# 780-00031_rev1_BlackFin_Shorting_Block.net
KiCad netlist of a schematic drawn in Altium Designer
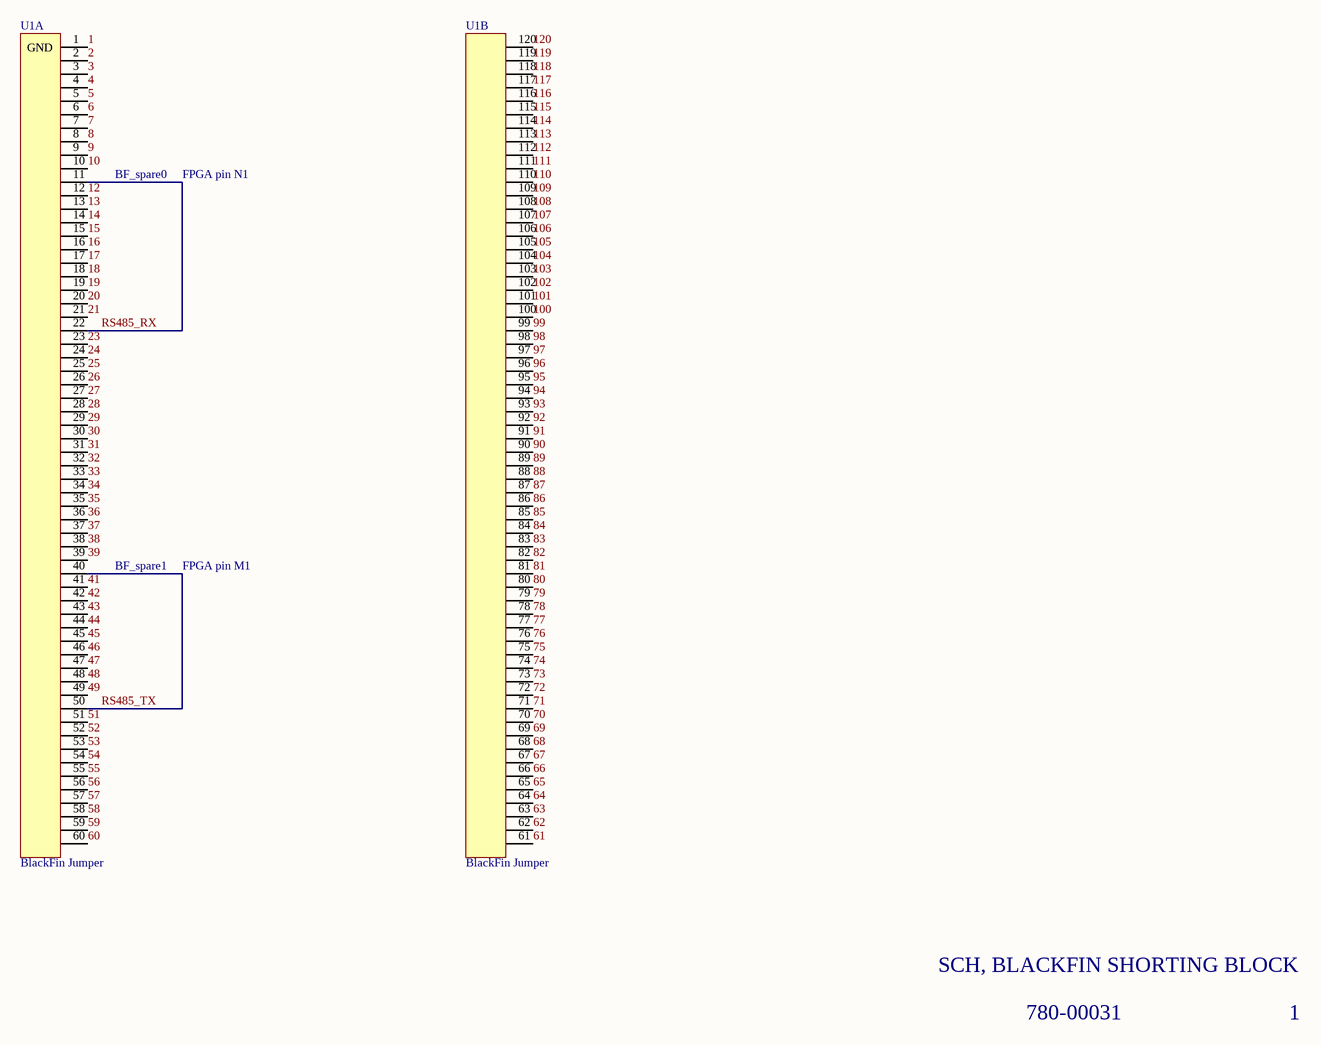
[diagram p0: 780-00031, rev1, BlackFin Shorting Block.SchDoc]

(export (version "E")
  (design (tool "Eeschema 10.0.6"))
  (components
    (comp (ref "U1")
      (value "BlackFin Jumper")
      (footprint "CM-BF5xx - Shorting Block")
      (description "Jumper to replace BF with shorting block")
      (libsource (lib "") (part "BlackFin Jumper_1"))
    )
  )
  (nets
    (net (code "1") (name "/1") (class "Default")
      (node (ref "U1") (pin "1") (pinfunction "GND_1") (pintype "passive"))
    )
    (net (code "2") (name "/2") (class "Default") (node (ref "U1") (pin "2") (pintype "passive")))
    (net (code "3") (name "/3") (class "Default") (node (ref "U1") (pin "3") (pintype "passive")))
    (net (code "4") (name "/4") (class "Default") (node (ref "U1") (pin "4") (pintype "passive")))
    (net (code "5") (name "/5") (class "Default") (node (ref "U1") (pin "5") (pintype "passive")))
    (net (code "6") (name "/6") (class "Default") (node (ref "U1") (pin "6") (pintype "passive")))
    (net (code "7") (name "/7") (class "Default") (node (ref "U1") (pin "7") (pintype "passive")))
    (net (code "8") (name "/8") (class "Default") (node (ref "U1") (pin "8") (pintype "passive")))
    (net (code "9") (name "/9") (class "Default") (node (ref "U1") (pin "9") (pintype "passive")))
    (net (code "10") (name "/10") (class "Default") (node (ref "U1") (pin "10") (pintype "passive")))
    (net (code "11") (name "/12") (class "Default") (node (ref "U1") (pin "12") (pintype "passive")))
    (net (code "12") (name "/13") (class "Default") (node (ref "U1") (pin "13") (pintype "passive")))
    (net (code "13") (name "/14") (class "Default") (node (ref "U1") (pin "14") (pintype "passive")))
    (net (code "14") (name "/15") (class "Default") (node (ref "U1") (pin "15") (pintype "passive")))
    (net (code "15") (name "/16") (class "Default") (node (ref "U1") (pin "16") (pintype "passive")))
    (net (code "16") (name "/17") (class "Default") (node (ref "U1") (pin "17") (pintype "passive")))
    (net (code "17") (name "/18") (class "Default") (node (ref "U1") (pin "18") (pintype "passive")))
    (net (code "18") (name "/19") (class "Default") (node (ref "U1") (pin "19") (pintype "passive")))
    (net (code "19") (name "/20") (class "Default") (node (ref "U1") (pin "20") (pintype "passive")))
    (net (code "20") (name "/21") (class "Default") (node (ref "U1") (pin "21") (pintype "passive")))
    (net (code "21") (name "/23") (class "Default") (node (ref "U1") (pin "23") (pintype "passive")))
    (net (code "22") (name "/24") (class "Default") (node (ref "U1") (pin "24") (pintype "passive")))
    (net (code "23") (name "/25") (class "Default") (node (ref "U1") (pin "25") (pintype "passive")))
    (net (code "24") (name "/26") (class "Default") (node (ref "U1") (pin "26") (pintype "passive")))
    (net (code "25") (name "/27") (class "Default") (node (ref "U1") (pin "27") (pintype "passive")))
    (net (code "26") (name "/28") (class "Default") (node (ref "U1") (pin "28") (pintype "passive")))
    (net (code "27") (name "/29") (class "Default") (node (ref "U1") (pin "29") (pintype "passive")))
    (net (code "28") (name "/30") (class "Default") (node (ref "U1") (pin "30") (pintype "passive")))
    (net (code "29") (name "/31") (class "Default") (node (ref "U1") (pin "31") (pintype "passive")))
    (net (code "30") (name "/32") (class "Default") (node (ref "U1") (pin "32") (pintype "passive")))
    (net (code "31") (name "/33") (class "Default") (node (ref "U1") (pin "33") (pintype "passive")))
    (net (code "32") (name "/34") (class "Default") (node (ref "U1") (pin "34") (pintype "passive")))
    (net (code "33") (name "/35") (class "Default") (node (ref "U1") (pin "35") (pintype "passive")))
    (net (code "34") (name "/36") (class "Default") (node (ref "U1") (pin "36") (pintype "passive")))
    (net (code "35") (name "/37") (class "Default") (node (ref "U1") (pin "37") (pintype "passive")))
    (net (code "36") (name "/38") (class "Default") (node (ref "U1") (pin "38") (pintype "passive")))
    (net (code "37") (name "/39") (class "Default") (node (ref "U1") (pin "39") (pintype "passive")))
    (net (code "38") (name "/41") (class "Default") (node (ref "U1") (pin "41") (pintype "passive")))
    (net (code "39") (name "/42") (class "Default") (node (ref "U1") (pin "42") (pintype "passive")))
    (net (code "40") (name "/43") (class "Default") (node (ref "U1") (pin "43") (pintype "passive")))
    (net (code "41") (name "/44") (class "Default") (node (ref "U1") (pin "44") (pintype "passive")))
    (net (code "42") (name "/45") (class "Default") (node (ref "U1") (pin "45") (pintype "passive")))
    (net (code "43") (name "/46") (class "Default") (node (ref "U1") (pin "46") (pintype "passive")))
    (net (code "44") (name "/47") (class "Default") (node (ref "U1") (pin "47") (pintype "passive")))
    (net (code "45") (name "/48") (class "Default") (node (ref "U1") (pin "48") (pintype "passive")))
    (net (code "46") (name "/49") (class "Default") (node (ref "U1") (pin "49") (pintype "passive")))
    (net (code "47") (name "/51") (class "Default") (node (ref "U1") (pin "51") (pintype "passive")))
    (net (code "48") (name "/52") (class "Default") (node (ref "U1") (pin "52") (pintype "passive")))
    (net (code "49") (name "/53") (class "Default") (node (ref "U1") (pin "53") (pintype "passive")))
    (net (code "50") (name "/54") (class "Default") (node (ref "U1") (pin "54") (pintype "passive")))
    (net (code "51") (name "/55") (class "Default") (node (ref "U1") (pin "55") (pintype "passive")))
    (net (code "52") (name "/56") (class "Default") (node (ref "U1") (pin "56") (pintype "passive")))
    (net (code "53") (name "/57") (class "Default") (node (ref "U1") (pin "57") (pintype "passive")))
    (net (code "54") (name "/58") (class "Default") (node (ref "U1") (pin "58") (pintype "passive")))
    (net (code "55") (name "/59") (class "Default") (node (ref "U1") (pin "59") (pintype "passive")))
    (net (code "56") (name "/60") (class "Default") (node (ref "U1") (pin "60") (pintype "passive")))
    (net (code "57") (name "/61") (class "Default") (node (ref "U1") (pin "61") (pintype "passive")))
    (net (code "58") (name "/62") (class "Default") (node (ref "U1") (pin "62") (pintype "passive")))
    (net (code "59") (name "/63") (class "Default") (node (ref "U1") (pin "63") (pintype "passive")))
    (net (code "60") (name "/64") (class "Default") (node (ref "U1") (pin "64") (pintype "passive")))
    (net (code "61") (name "/65") (class "Default") (node (ref "U1") (pin "65") (pintype "passive")))
    (net (code "62") (name "/66") (class "Default") (node (ref "U1") (pin "66") (pintype "passive")))
    (net (code "63") (name "/67") (class "Default") (node (ref "U1") (pin "67") (pintype "passive")))
    (net (code "64") (name "/68") (class "Default") (node (ref "U1") (pin "68") (pintype "passive")))
    (net (code "65") (name "/69") (class "Default") (node (ref "U1") (pin "69") (pintype "passive")))
    (net (code "66") (name "/70") (class "Default") (node (ref "U1") (pin "70") (pintype "passive")))
    (net (code "67") (name "/71") (class "Default") (node (ref "U1") (pin "71") (pintype "passive")))
    (net (code "68") (name "/72") (class "Default") (node (ref "U1") (pin "72") (pintype "passive")))
    (net (code "69") (name "/73") (class "Default") (node (ref "U1") (pin "73") (pintype "passive")))
    (net (code "70") (name "/74") (class "Default") (node (ref "U1") (pin "74") (pintype "passive")))
    (net (code "71") (name "/75") (class "Default") (node (ref "U1") (pin "75") (pintype "passive")))
    (net (code "72") (name "/76") (class "Default") (node (ref "U1") (pin "76") (pintype "passive")))
    (net (code "73") (name "/77") (class "Default") (node (ref "U1") (pin "77") (pintype "passive")))
    (net (code "74") (name "/78") (class "Default") (node (ref "U1") (pin "78") (pintype "passive")))
    (net (code "75") (name "/79") (class "Default") (node (ref "U1") (pin "79") (pintype "passive")))
    (net (code "76") (name "/80") (class "Default") (node (ref "U1") (pin "80") (pintype "passive")))
    (net (code "77") (name "/81") (class "Default") (node (ref "U1") (pin "81") (pintype "passive")))
    (net (code "78") (name "/82") (class "Default") (node (ref "U1") (pin "82") (pintype "passive")))
    (net (code "79") (name "/83") (class "Default") (node (ref "U1") (pin "83") (pintype "passive")))
    (net (code "80") (name "/84") (class "Default") (node (ref "U1") (pin "84") (pintype "passive")))
    (net (code "81") (name "/85") (class "Default") (node (ref "U1") (pin "85") (pintype "passive")))
    (net (code "82") (name "/86") (class "Default") (node (ref "U1") (pin "86") (pintype "passive")))
    (net (code "83") (name "/87") (class "Default") (node (ref "U1") (pin "87") (pintype "passive")))
    (net (code "84") (name "/88") (class "Default") (node (ref "U1") (pin "88") (pintype "passive")))
    (net (code "85") (name "/89") (class "Default") (node (ref "U1") (pin "89") (pintype "passive")))
    (net (code "86") (name "/90") (class "Default") (node (ref "U1") (pin "90") (pintype "passive")))
    (net (code "87") (name "/91") (class "Default") (node (ref "U1") (pin "91") (pintype "passive")))
    (net (code "88") (name "/92") (class "Default") (node (ref "U1") (pin "92") (pintype "passive")))
    (net (code "89") (name "/93") (class "Default") (node (ref "U1") (pin "93") (pintype "passive")))
    (net (code "90") (name "/94") (class "Default") (node (ref "U1") (pin "94") (pintype "passive")))
    (net (code "91") (name "/95") (class "Default") (node (ref "U1") (pin "95") (pintype "passive")))
    (net (code "92") (name "/96") (class "Default") (node (ref "U1") (pin "96") (pintype "passive")))
    (net (code "93") (name "/97") (class "Default") (node (ref "U1") (pin "97") (pintype "passive")))
    (net (code "94") (name "/98") (class "Default") (node (ref "U1") (pin "98") (pintype "passive")))
    (net (code "95") (name "/99") (class "Default") (node (ref "U1") (pin "99") (pintype "passive")))
    (net (code "96") (name "/100") (class "Default") (node (ref "U1") (pin "100") (pintype "passive")))
    (net (code "97") (name "/101") (class "Default") (node (ref "U1") (pin "101") (pintype "passive")))
    (net (code "98") (name "/102") (class "Default") (node (ref "U1") (pin "102") (pintype "passive")))
    (net (code "99") (name "/103") (class "Default") (node (ref "U1") (pin "103") (pintype "passive")))
    (net (code "100") (name "/104") (class "Default") (node (ref "U1") (pin "104") (pintype "passive")))
    (net (code "101") (name "/105") (class "Default") (node (ref "U1") (pin "105") (pintype "passive")))
    (net (code "102") (name "/106") (class "Default") (node (ref "U1") (pin "106") (pintype "passive")))
    (net (code "103") (name "/107") (class "Default") (node (ref "U1") (pin "107") (pintype "passive")))
    (net (code "104") (name "/108") (class "Default") (node (ref "U1") (pin "108") (pintype "passive")))
    (net (code "105") (name "/109") (class "Default") (node (ref "U1") (pin "109") (pintype "passive")))
    (net (code "106") (name "/110") (class "Default") (node (ref "U1") (pin "110") (pintype "passive")))
    (net (code "107") (name "/111") (class "Default") (node (ref "U1") (pin "111") (pintype "passive")))
    (net (code "108") (name "/112") (class "Default") (node (ref "U1") (pin "112") (pintype "passive")))
    (net (code "109") (name "/113") (class "Default") (node (ref "U1") (pin "113") (pintype "passive")))
    (net (code "110") (name "/114") (class "Default") (node (ref "U1") (pin "114") (pintype "passive")))
    (net (code "111") (name "/115") (class "Default") (node (ref "U1") (pin "115") (pintype "passive")))
    (net (code "112") (name "/116") (class "Default") (node (ref "U1") (pin "116") (pintype "passive")))
    (net (code "113") (name "/117") (class "Default") (node (ref "U1") (pin "117") (pintype "passive")))
    (net (code "114") (name "/118") (class "Default") (node (ref "U1") (pin "118") (pintype "passive")))
    (net (code "115") (name "/119") (class "Default") (node (ref "U1") (pin "119") (pintype "passive")))
    (net (code "116") (name "/120") (class "Default") (node (ref "U1") (pin "120") (pintype "passive")))
    (net (code "117") (name "/RS485_RX") (class "Default")
      (node (ref "U1") (pin "11") (pintype "passive"))
      (node (ref "U1") (pin "22") (pintype "passive"))
    )
    (net (code "118") (name "/RS485_TX") (class "Default")
      (node (ref "U1") (pin "40") (pintype "passive"))
      (node (ref "U1") (pin "50") (pintype "passive"))
    )
  )
)
